# OpenTCUSandwich.net
KiCad netlist of a schematic drawn in EasyEDA
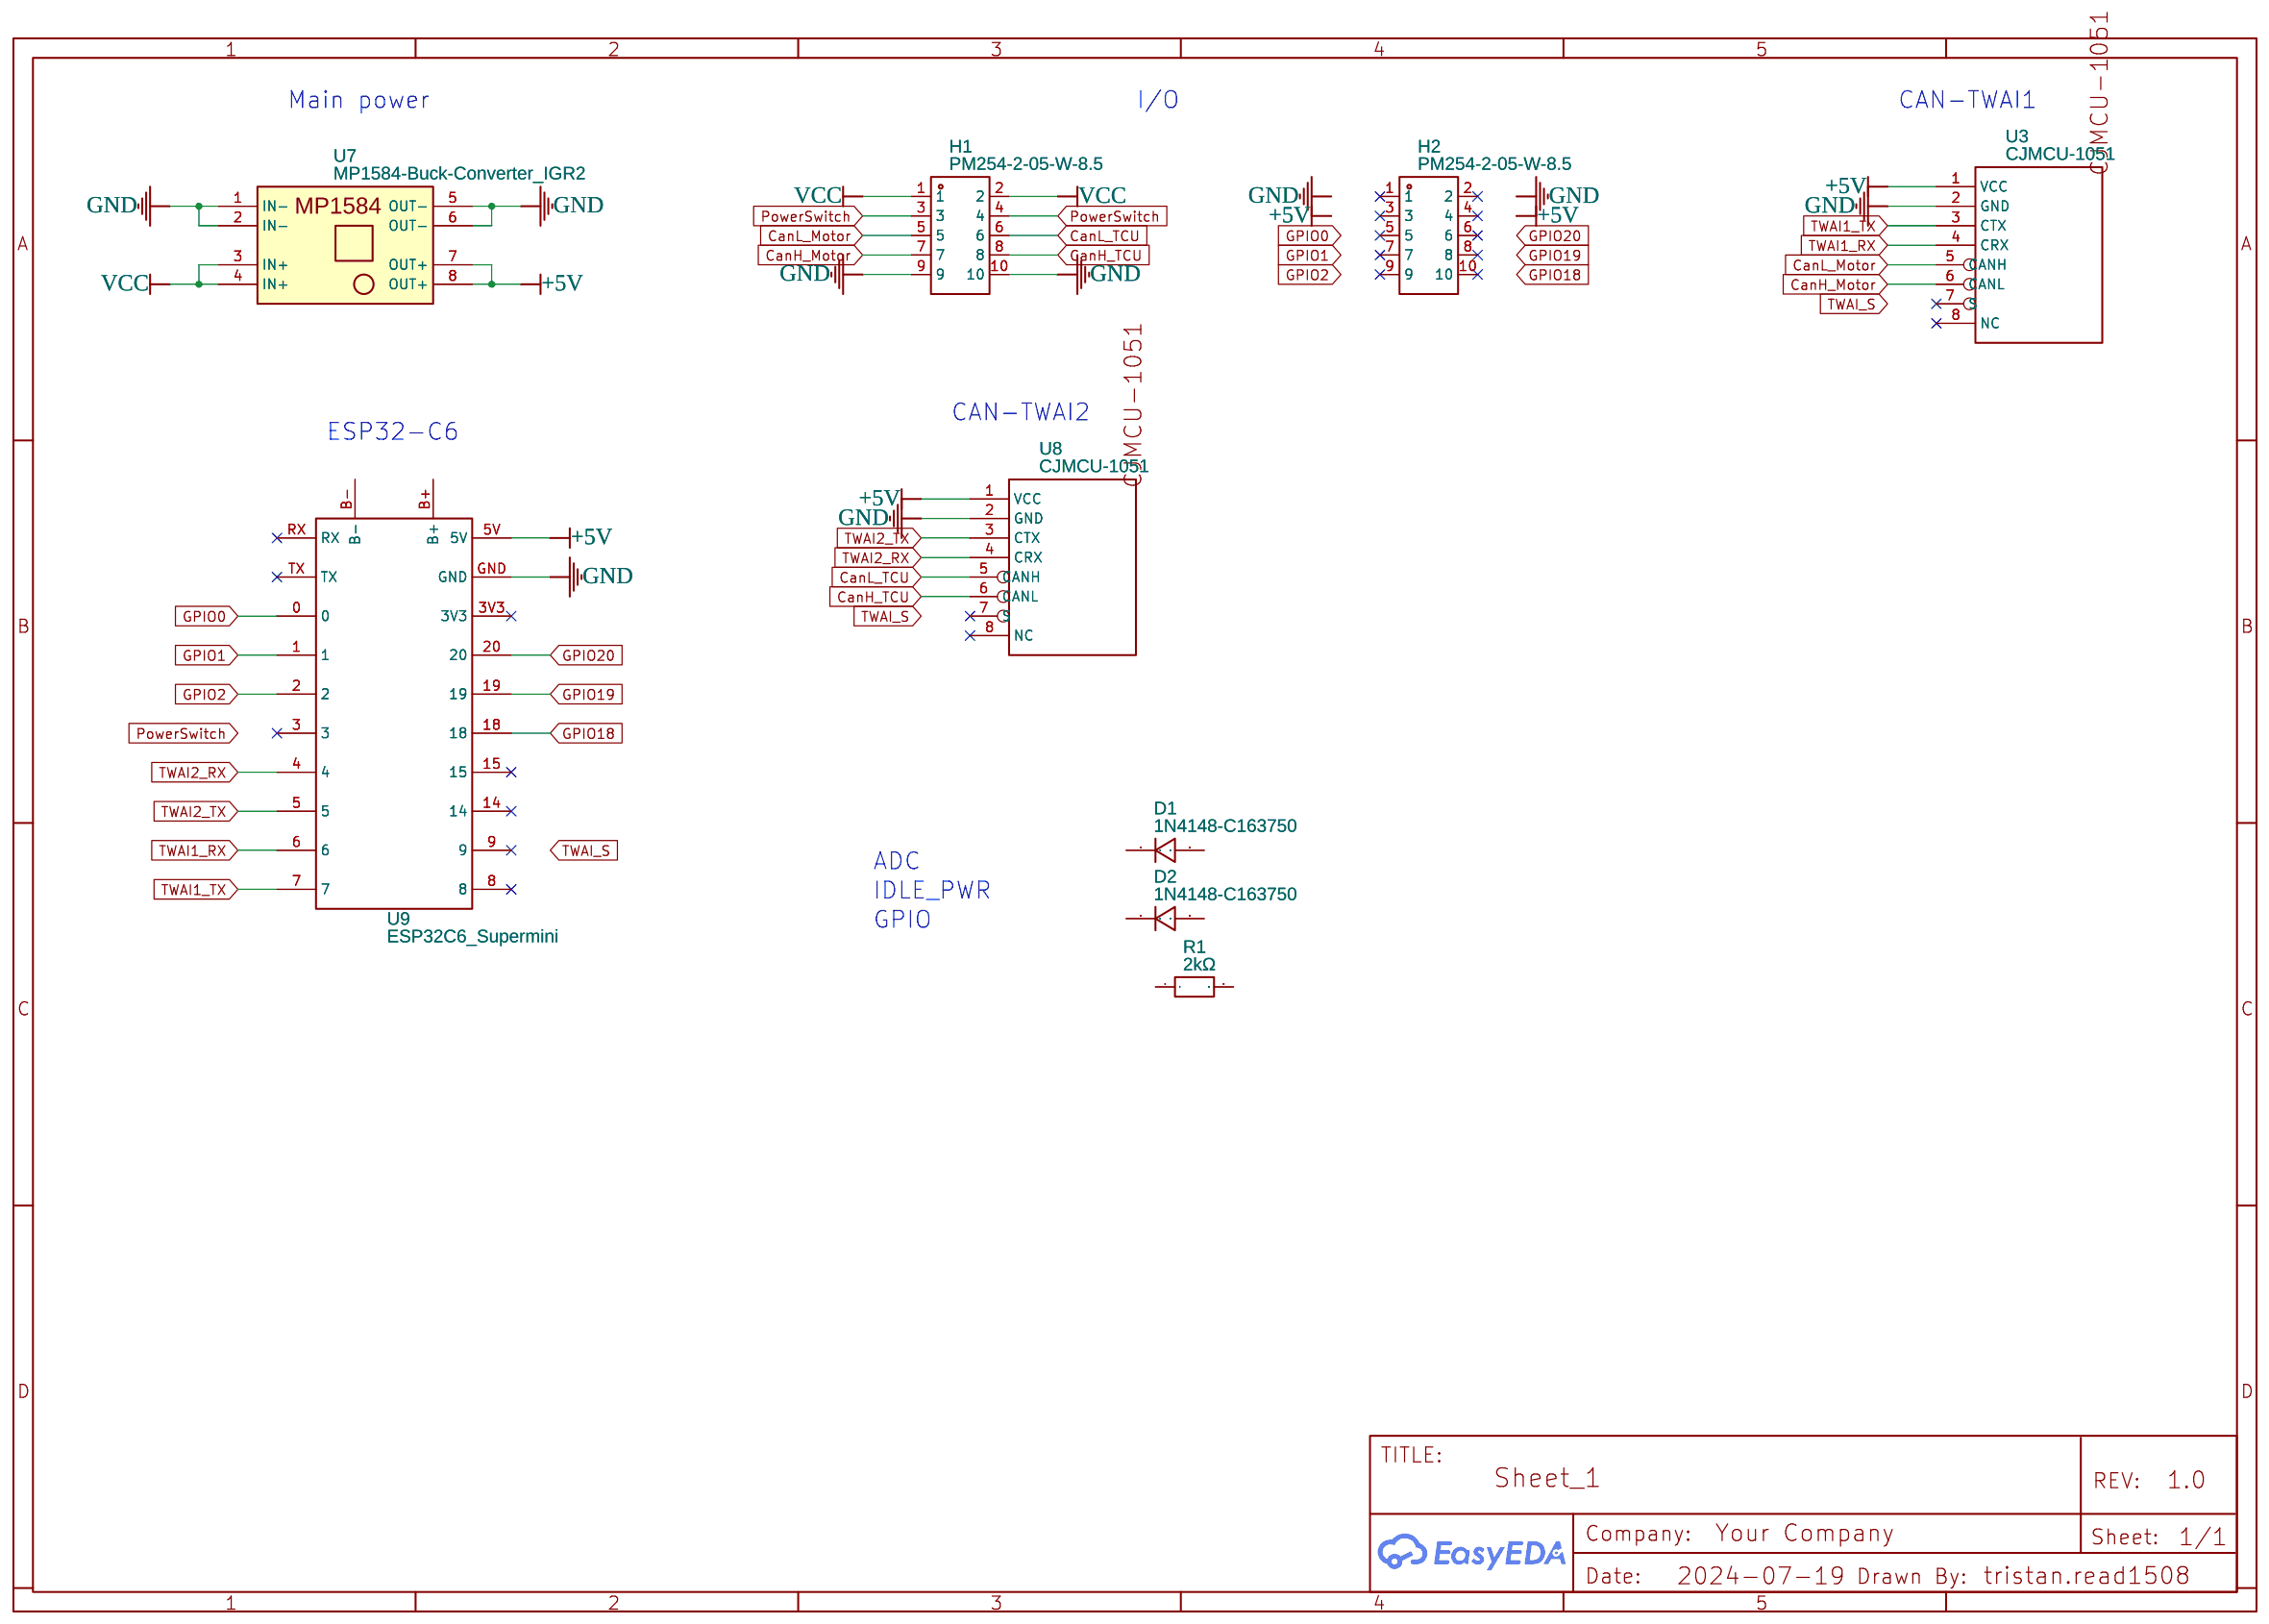
[diagram p0: schematic sheet]

(export (version "E")
  (design (tool "Eeschema 10.0.6"))
  (components
    (comp (ref "D1")
      (value "1N4148-C163750")
      (fields (field (name "Manufacturer Part") "1N4148") (field (name "Manufacturer") "FMS(美丽微)"))
      (libsource (lib "") (part "1N4148-C163750"))
    )
    (comp (ref "D2")
      (value "1N4148-C163750")
      (fields (field (name "Manufacturer Part") "1N4148") (field (name "Manufacturer") "FMS(美丽微)"))
      (libsource (lib "") (part "1N4148-C163750"))
    )
    (comp (ref "H1")
      (value "PM254-2-05-W-8.5")
      (fields (field (name "Manufacturer") "HCTL(华灿天禄)"))
      (libsource (lib "") (part "PM254-2-05-W-8.5"))
    )
    (comp (ref "H2")
      (value "PM254-2-05-W-8.5")
      (fields (field (name "Manufacturer") "HCTL(华灿天禄)"))
      (libsource (lib "") (part "PM254-2-05-W-8.5"))
    )
    (comp (ref "R1")
      (value "2kΩ")
      (fields (field (name "Manufacturer Part") "RN1/4W2KFT/BA1") (field (name "Manufacturer") "Tyohm(幸亚电阻)"))
      (libsource (lib "") (part "RN 1/4W 2K F T/B A1"))
    )
    (comp (ref "U3") (value "CJMCU-1051") (libsource (lib "") (part "CJMCU-1051")))
    (comp (ref "U7")
      (value "MP1584-Buck-Converter_IGR2")
      (fields (field (name "Manufacturer Part") "MP1584EN"))
      (libsource (lib "") (part "MP1584-Buck-Converter_IGR2"))
    )
    (comp (ref "U8") (value "CJMCU-1051") (libsource (lib "") (part "CJMCU-1051")))
    (comp (ref "U9") (value "ESP32C6_Supermini") (libsource (lib "") (part "ESP32C6_Supermini")))
  )
  (nets
    (net (code "1") (name "+5V") (class "Default")
      (node (ref "U3") (pin "1") (pinfunction "VCC_1") (pintype "unspecified"))
      (node (ref "U7") (pin "7") (pinfunction "OUT+_7") (pintype "unspecified"))
      (node (ref "U7") (pin "8") (pinfunction "OUT+_8") (pintype "unspecified"))
      (node (ref "U8") (pin "1") (pinfunction "VCC_1") (pintype "unspecified"))
      (node (ref "U9") (pin "5V") (pinfunction "5V_5V") (pintype "passive"))
    )
    (net (code "2") (name "CanH_Motor") (class "Default")
      (node (ref "H1") (pin "7") (pinfunction "7_7") (pintype "unspecified"))
      (node (ref "U3") (pin "6") (pinfunction "CANL_6") (pintype "unspecified"))
    )
    (net (code "3") (name "CanH_TCU") (class "Default")
      (node (ref "H1") (pin "8") (pinfunction "8_8") (pintype "unspecified"))
      (node (ref "U8") (pin "6") (pinfunction "CANL_6") (pintype "unspecified"))
    )
    (net (code "4") (name "CanL_Motor") (class "Default")
      (node (ref "H1") (pin "5") (pinfunction "5_5") (pintype "unspecified"))
      (node (ref "U3") (pin "5") (pinfunction "CANH_5") (pintype "unspecified"))
    )
    (net (code "5") (name "CanL_TCU") (class "Default")
      (node (ref "H1") (pin "6") (pinfunction "6_6") (pintype "unspecified"))
      (node (ref "U8") (pin "5") (pinfunction "CANH_5") (pintype "unspecified"))
    )
    (net (code "6") (name "GND") (class "Default")
      (node (ref "H1") (pin "10") (pinfunction "10_10") (pintype "unspecified"))
      (node (ref "H1") (pin "9") (pinfunction "9_9") (pintype "unspecified"))
      (node (ref "U3") (pin "2") (pinfunction "GND_2") (pintype "unspecified"))
      (node (ref "U7") (pin "1") (pinfunction "IN-_1") (pintype "unspecified"))
      (node (ref "U7") (pin "2") (pinfunction "IN-_2") (pintype "unspecified"))
      (node (ref "U7") (pin "5") (pinfunction "OUT-_5") (pintype "unspecified"))
      (node (ref "U7") (pin "6") (pinfunction "OUT-_6") (pintype "unspecified"))
      (node (ref "U8") (pin "2") (pinfunction "GND_2") (pintype "unspecified"))
      (node (ref "U9") (pin "GND") (pinfunction "GND_GND") (pintype "passive"))
    )
    (net (code "7") (name "GPIO0") (class "Default")
      (node (ref "U9") (pin "0") (pinfunction "0_0") (pintype "bidirectional"))
    )
    (net (code "8") (name "GPIO1") (class "Default")
      (node (ref "U9") (pin "1") (pinfunction "1_1") (pintype "bidirectional"))
    )
    (net (code "9") (name "GPIO2") (class "Default")
      (node (ref "U9") (pin "2") (pinfunction "2_2") (pintype "bidirectional"))
    )
    (net (code "10") (name "GPIO18") (class "Default")
      (node (ref "U9") (pin "18") (pinfunction "18_18") (pintype "unspecified"))
    )
    (net (code "11") (name "GPIO19") (class "Default")
      (node (ref "U9") (pin "19") (pinfunction "19_19") (pintype "unspecified"))
    )
    (net (code "12") (name "GPIO20") (class "Default")
      (node (ref "U9") (pin "20") (pinfunction "20_20") (pintype "unspecified"))
    )
    (net (code "13") (name "PowerSwitch") (class "Default")
      (node (ref "H1") (pin "3") (pinfunction "3_3") (pintype "unspecified"))
      (node (ref "H1") (pin "4") (pinfunction "4_4") (pintype "unspecified"))
    )
    (net (code "14") (name "TWAI1_RX") (class "Default")
      (node (ref "U3") (pin "4") (pinfunction "CRX_4") (pintype "unspecified"))
      (node (ref "U9") (pin "6") (pinfunction "6_6") (pintype "bidirectional"))
    )
    (net (code "15") (name "TWAI1_TX") (class "Default")
      (node (ref "U3") (pin "3") (pinfunction "CTX_3") (pintype "unspecified"))
      (node (ref "U9") (pin "7") (pinfunction "7_7") (pintype "bidirectional"))
    )
    (net (code "16") (name "TWAI2_RX") (class "Default")
      (node (ref "U8") (pin "4") (pinfunction "CRX_4") (pintype "unspecified"))
      (node (ref "U9") (pin "4") (pinfunction "4_4") (pintype "bidirectional"))
    )
    (net (code "17") (name "TWAI2_TX") (class "Default")
      (node (ref "U8") (pin "3") (pinfunction "CTX_3") (pintype "unspecified"))
      (node (ref "U9") (pin "5") (pinfunction "5_5") (pintype "bidirectional"))
    )
    (net (code "19") (name "VCC") (class "Default")
      (node (ref "H1") (pin "1") (pinfunction "1_1") (pintype "unspecified"))
      (node (ref "H1") (pin "2") (pinfunction "2_2") (pintype "unspecified"))
      (node (ref "U7") (pin "3") (pinfunction "IN+_3") (pintype "unspecified"))
      (node (ref "U7") (pin "4") (pinfunction "IN+_4") (pintype "unspecified"))
    )
    (net (code "20") (name "unconnected-(D1-Pad1)") (class "Default")
      (node (ref "D1") (pin "1") (pinfunction "1_1") (pintype "unspecified"))
    )
    (net (code "21") (name "unconnected-(D1-Pad2)") (class "Default")
      (node (ref "D1") (pin "2") (pinfunction "2_2") (pintype "unspecified"))
    )
    (net (code "22") (name "unconnected-(D2-Pad1)") (class "Default")
      (node (ref "D2") (pin "1") (pinfunction "1_1") (pintype "unspecified"))
    )
    (net (code "23") (name "unconnected-(D2-Pad2)") (class "Default")
      (node (ref "D2") (pin "2") (pinfunction "2_2") (pintype "unspecified"))
    )
    (net (code "24") (name "unconnected-(H2-Pad1)") (class "Default")
      (node (ref "H2") (pin "1") (pinfunction "1_1") (pintype "unspecified+no_connect"))
    )
    (net (code "25") (name "unconnected-(H2-Pad2)") (class "Default")
      (node (ref "H2") (pin "2") (pinfunction "2_2") (pintype "unspecified+no_connect"))
    )
    (net (code "26") (name "unconnected-(H2-Pad3)") (class "Default")
      (node (ref "H2") (pin "3") (pinfunction "3_3") (pintype "unspecified+no_connect"))
    )
    (net (code "27") (name "unconnected-(H2-Pad4)") (class "Default")
      (node (ref "H2") (pin "4") (pinfunction "4_4") (pintype "unspecified+no_connect"))
    )
    (net (code "28") (name "unconnected-(H2-Pad5)") (class "Default")
      (node (ref "H2") (pin "5") (pinfunction "5_5") (pintype "unspecified+no_connect"))
    )
    (net (code "29") (name "unconnected-(H2-Pad6)") (class "Default")
      (node (ref "H2") (pin "6") (pinfunction "6_6") (pintype "unspecified+no_connect"))
    )
    (net (code "30") (name "unconnected-(H2-Pad7)") (class "Default")
      (node (ref "H2") (pin "7") (pinfunction "7_7") (pintype "unspecified+no_connect"))
    )
    (net (code "31") (name "unconnected-(H2-Pad8)") (class "Default")
      (node (ref "H2") (pin "8") (pinfunction "8_8") (pintype "unspecified+no_connect"))
    )
    (net (code "32") (name "unconnected-(H2-Pad9)") (class "Default")
      (node (ref "H2") (pin "9") (pinfunction "9_9") (pintype "unspecified+no_connect"))
    )
    (net (code "33") (name "unconnected-(H2-Pad10)") (class "Default")
      (node (ref "H2") (pin "10") (pinfunction "10_10") (pintype "unspecified+no_connect"))
    )
    (net (code "34") (name "unconnected-(R1-Pad1)") (class "Default")
      (node (ref "R1") (pin "1") (pinfunction "1_1") (pintype "unspecified"))
    )
    (net (code "35") (name "unconnected-(R1-Pad2)") (class "Default")
      (node (ref "R1") (pin "2") (pinfunction "2_2") (pintype "unspecified"))
    )
    (net (code "36") (name "unconnected-(U3-NC-Pad8)") (class "Default")
      (node (ref "U3") (pin "8") (pinfunction "NC_8") (pintype "unspecified+no_connect"))
    )
    (net (code "37") (name "unconnected-(U3-S-Pad7)") (class "Default")
      (node (ref "U3") (pin "7") (pinfunction "S_7") (pintype "unspecified+no_connect"))
    )
    (net (code "38") (name "unconnected-(U8-NC-Pad8)") (class "Default")
      (node (ref "U8") (pin "8") (pinfunction "NC_8") (pintype "unspecified+no_connect"))
    )
    (net (code "39") (name "unconnected-(U8-S-Pad7)") (class "Default")
      (node (ref "U8") (pin "7") (pinfunction "S_7") (pintype "unspecified+no_connect"))
    )
    (net (code "40") (name "unconnected-(U9-Pad3)") (class "Default")
      (node (ref "U9") (pin "3") (pinfunction "3_3") (pintype "bidirectional+no_connect"))
    )
    (net (code "41") (name "unconnected-(U9-Pad3V3)") (class "Default")
      (node (ref "U9") (pin "3V3") (pinfunction "3V3_3V3") (pintype "passive+no_connect"))
    )
    (net (code "42") (name "unconnected-(U9-Pad8)") (class "Default")
      (node (ref "U9") (pin "8") (pinfunction "8_8") (pintype "unspecified+no_connect"))
    )
    (net (code "43") (name "unconnected-(U9-Pad9)") (class "Default")
      (node (ref "U9") (pin "9") (pinfunction "9_9") (pintype "unspecified+no_connect"))
    )
    (net (code "44") (name "unconnected-(U9-Pad14)") (class "Default")
      (node (ref "U9") (pin "14") (pinfunction "14_14") (pintype "unspecified+no_connect"))
    )
    (net (code "45") (name "unconnected-(U9-Pad15)") (class "Default")
      (node (ref "U9") (pin "15") (pinfunction "15_15") (pintype "unspecified+no_connect"))
    )
    (net (code "46") (name "unconnected-(U9-PadB+)") (class "Default")
      (node (ref "U9") (pin "B+") (pinfunction "B+_B+") (pintype "unspecified"))
    )
    (net (code "47") (name "unconnected-(U9-PadB-)") (class "Default")
      (node (ref "U9") (pin "B-") (pinfunction "B-_B-") (pintype "unspecified"))
    )
    (net (code "48") (name "unconnected-(U9-PadRX)") (class "Default")
      (node (ref "U9") (pin "RX") (pinfunction "RX_RX") (pintype "unspecified+no_connect"))
    )
    (net (code "49") (name "unconnected-(U9-PadTX)") (class "Default")
      (node (ref "U9") (pin "TX") (pinfunction "TX_TX") (pintype "unspecified+no_connect"))
    )
  )
)
